# Power_Distribution_-_Charger_and_Rear_Ca.net
KiCad netlist of a schematic drawn in Altium Designer
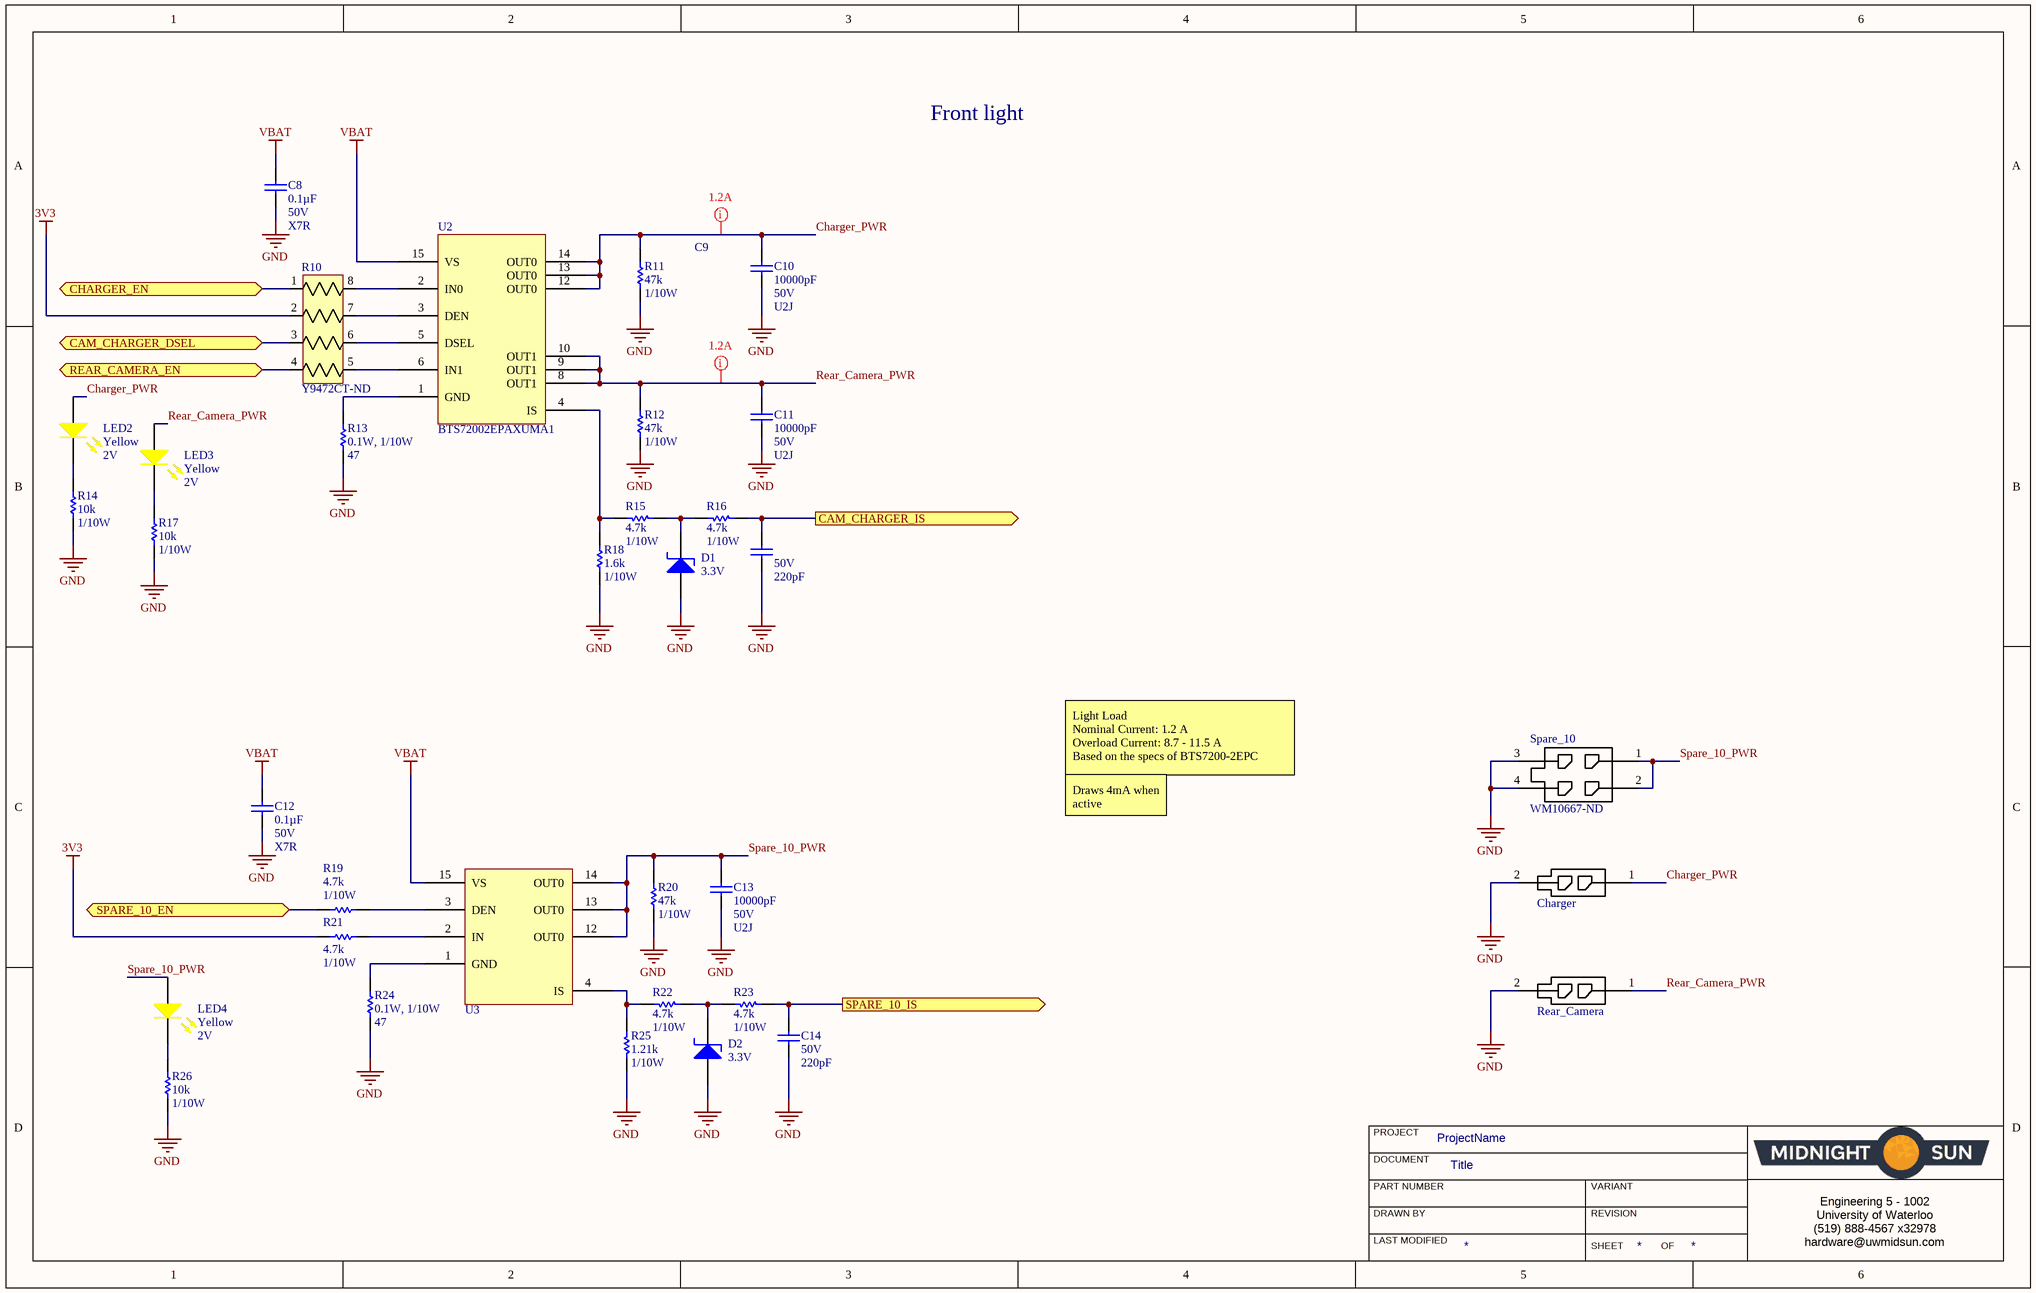
[diagram p0: Power Distribution - Charger and Rear Camera.SchDoc]

(export (version "E")
  (design (tool "Eeschema 10.0.6"))
  (components
    (comp (ref "C8")
      (value "CAP CER 0.1UF 50V 10% X7R 0603")
      (footprint "CAP, 0603")
      (description "0.10µF ±10% 50V Ceramic Capacitor X7R 0603 (1608 Metric)")
      (fields
        (field (name "TOLERANCE") "±10%")
        (field (name "CAPACITANCE") "0.1µF")
        (field (name "VOLTAGE") "50V")
        (field (name "TEMPERATURE COEFFICIENT") "X7R")
      )
      (libsource (lib "Schematic Diagrams") (part "CAP CER 0.1UF 50V 10% X7R 0603"))
    )
    (comp (ref "C9")
      (value "CAP CER 220PF 50V C0G/NP0 0603")
      (footprint "CAP, 0603")
      (description "220pF ±5% 50V Ceramic Capacitor C0G, NP0 0603 (1608 Metric)")
      (fields
        (field (name "MANUFACTURER") "KEMET")
        (field (name "TOLERANCE") "5%")
        (field (name "VOLTAGE RATING") "50V")
        (field (name "CAPACITANCE") "220pF")
      )
      (libsource (lib "Schematic Diagrams") (part "CAP CER 220PF 50V C0G/NP0 0603"))
    )
    (comp (ref "C10")
      (value "CAP CER 10nF 50V 5% X7R 0603")
      (footprint "CAP, 0603")
      (description "10000pF ±5% 50V Ceramic Capacitor U2J 0603 (1608 Metric)")
      (fields
        (field (name "TOLERANCE") "±5%")
        (field (name "CAPACITANCE") "10000pF")
        (field (name "VOLTAGE") "50V")
        (field (name "TEMPERATURE COEFFICIENT") "U2J")
      )
      (libsource (lib "Schematic Diagrams") (part "CAP CER 10nF 50V 5% X7R 0603"))
    )
    (comp (ref "C11")
      (value "CAP CER 10nF 50V 5% X7R 0603")
      (footprint "CAP, 0603")
      (description "10000pF ±5% 50V Ceramic Capacitor U2J 0603 (1608 Metric)")
      (fields
        (field (name "TOLERANCE") "±5%")
        (field (name "CAPACITANCE") "10000pF")
        (field (name "VOLTAGE") "50V")
        (field (name "TEMPERATURE COEFFICIENT") "U2J")
      )
      (libsource (lib "Schematic Diagrams") (part "CAP CER 10nF 50V 5% X7R 0603"))
    )
    (comp (ref "C12")
      (value "CAP CER 0.1UF 50V 10% X7R 0603")
      (footprint "CAP, 0603")
      (description "0.10µF ±10% 50V Ceramic Capacitor X7R 0603 (1608 Metric)")
      (fields
        (field (name "TOLERANCE") "±10%")
        (field (name "CAPACITANCE") "0.1µF")
        (field (name "VOLTAGE") "50V")
        (field (name "TEMPERATURE COEFFICIENT") "X7R")
      )
      (libsource (lib "Schematic Diagrams") (part "CAP CER 0.1UF 50V 10% X7R 0603"))
    )
    (comp (ref "C13")
      (value "CAP CER 10nF 50V 5% X7R 0603")
      (footprint "CAP, 0603")
      (description "10000pF ±5% 50V Ceramic Capacitor U2J 0603 (1608 Metric)")
      (fields
        (field (name "TOLERANCE") "±5%")
        (field (name "CAPACITANCE") "10000pF")
        (field (name "VOLTAGE") "50V")
        (field (name "TEMPERATURE COEFFICIENT") "U2J")
      )
      (libsource (lib "Schematic Diagrams") (part "CAP CER 10nF 50V 5% X7R 0603"))
    )
    (comp (ref "C14")
      (value "CAP CER 220PF 50V C0G/NP0 0603")
      (footprint "CAP, 0603")
      (description "220pF ±5% 50V Ceramic Capacitor C0G, NP0 0603 (1608 Metric)")
      (fields
        (field (name "MANUFACTURER") "KEMET")
        (field (name "TOLERANCE") "5%")
        (field (name "VOLTAGE RATING") "50V")
        (field (name "CAPACITANCE") "220pF")
      )
      (libsource (lib "Schematic Diagrams") (part "CAP CER 220PF 50V C0G/NP0 0603"))
    )
    (comp (ref "Charger")
      (value "CONN 2POS MICRO-FIT 3mm")
      (footprint "CONN, 2POS MICRO-FIT")
      (description "Connector Header Through Hole 2 position")
      (fields (field (name "MANUFACTURER") "Molex") (field (name "MANUFACTURER PART NUMBER") "43045-0227"))
      (libsource (lib "Schematic Diagrams") (part "CONN 2POS MICRO-FIT 3mm"))
    )
    (comp (ref "D1")
      (value "DIODE ZENER 3.3V 200MW SOD323")
      (footprint "sod-323")
      (description "Zener Diode 3.3V 200mW ±5% Surface Mount SOD-323")
      (fields (field (name "VOLTAGE") "3.3V"))
      (libsource (lib "Schematic Diagrams") (part "DIODE ZENER 3.3V 200MW SOD323"))
    )
    (comp (ref "D2")
      (value "DIODE ZENER 3.3V 200MW SOD323")
      (footprint "sod-323")
      (description "Zener Diode 3.3V 200mW ±5% Surface Mount SOD-323")
      (fields (field (name "VOLTAGE") "3.3V"))
      (libsource (lib "Schematic Diagrams") (part "DIODE ZENER 3.3V 200MW SOD323"))
    )
    (comp (ref "LED2")
      (value "LED YELLOW CLEAR 2.1V 0603")
      (footprint "LED_0603")
      (description "Yellow 590nm LED Indication - Discrete 2V 0603 (1608 Metric)")
      (fields
        (field (name "MANUFACTURER") "Wurth Electronics Inc.")
        (field (name "MANUFACTURER PART NUMBER") "150060YS75000")
        (field (name "COLOR") "Yellow")
        (field (name "VOLTAGE - FORWARD (VF) (TYP)") "2V")
      )
      (libsource (lib "Schematic Diagrams") (part "LED YELLOW CLEAR 2.1V 0603"))
    )
    (comp (ref "LED3")
      (value "LED YELLOW CLEAR 2.1V 0603")
      (footprint "LED_0603")
      (description "Yellow 590nm LED Indication - Discrete 2V 0603 (1608 Metric)")
      (fields
        (field (name "MANUFACTURER") "Wurth Electronics Inc.")
        (field (name "MANUFACTURER PART NUMBER") "150060YS75000")
        (field (name "COLOR") "Yellow")
        (field (name "VOLTAGE - FORWARD (VF) (TYP)") "2V")
      )
      (libsource (lib "Schematic Diagrams") (part "LED YELLOW CLEAR 2.1V 0603"))
    )
    (comp (ref "LED4")
      (value "LED YELLOW CLEAR 2.1V 0603")
      (footprint "LED_0603")
      (description "Yellow 590nm LED Indication - Discrete 2V 0603 (1608 Metric)")
      (fields
        (field (name "MANUFACTURER") "Wurth Electronics Inc.")
        (field (name "MANUFACTURER PART NUMBER") "150060YS75000")
        (field (name "COLOR") "Yellow")
        (field (name "VOLTAGE - FORWARD (VF) (TYP)") "2V")
      )
      (libsource (lib "Schematic Diagrams") (part "LED YELLOW CLEAR 2.1V 0603"))
    )
    (comp (ref "R10")
      (value "RES ARRAY 4 RES 4.7K OHM 1206")
      (footprint "RES ARRAY 4RES 1206")
      (fields (field (name "TOLERANCE") "±5%") (field (name "SUPPLIER PART NUMBER 1") "Y9472CT-ND"))
      (libsource (lib "Schematic Diagrams") (part "RES ARRAY 4 RES 4.7K OHM 1206"))
    )
    (comp (ref "R11")
      (value "RES 47K OHM 1% 1/10W 0603")
      (footprint "RES, 0603")
      (description "47 kOhms ±1% 0.1W, 1/10W Chip Resistor 0603 (1608 Metric) Automotive AEC-Q200 Thick Film")
      (fields
        (field (name "MANUFACTURER") "Panasonic")
        (field (name "MANUFACTURER PART NUMBER") "ERJ3EKF4702V")
        (field (name "RESISTANCE") "47k")
        (field (name "POWER RATING") "1/10W")
      )
      (libsource (lib "Schematic Diagrams") (part "RES 47K OHM 1% 1/10W 0603"))
    )
    (comp (ref "R12")
      (value "RES 47K OHM 1% 1/10W 0603")
      (footprint "RES, 0603")
      (description "47 kOhms ±1% 0.1W, 1/10W Chip Resistor 0603 (1608 Metric) Automotive AEC-Q200 Thick Film")
      (fields
        (field (name "MANUFACTURER") "Panasonic")
        (field (name "MANUFACTURER PART NUMBER") "ERJ3EKF4702V")
        (field (name "RESISTANCE") "47k")
        (field (name "POWER RATING") "1/10W")
      )
      (libsource (lib "Schematic Diagrams") (part "RES 47K OHM 1% 1/10W 0603"))
    )
    (comp (ref "R13")
      (value "RES SMD 47 OHM 1% 1/10W 0603")
      (footprint "RES, 0603")
      (fields
        (field (name "TOLERANCE") "±1%")
        (field (name "POWER (WATTS)") "0.1W, 1/10W")
        (field (name "VALUES") "47")
      )
      (libsource (lib "Schematic Diagrams") (part "RES SMD 47 OHM 1% 1/10W 0603"))
    )
    (comp (ref "R14")
      (value "RES 10K OHM 1% 1/10W 0603")
      (footprint "RES, 0603")
      (description "RES SMD 10K OHM 1% 1/10W 0603")
      (fields
        (field (name "TOLERANCE") "±1%")
        (field (name "RESISTANCE") "10k")
        (field (name "POWER") "1/10W")
      )
      (libsource (lib "Schematic Diagrams") (part "RES 10K OHM 1% 1/10W 0603"))
    )
    (comp (ref "R15")
      (value "RES 4.7K OHM 1% 1/10W 0603")
      (footprint "RES, 0603")
      (description "4.7k Ohm ±1% 0.1W, 1/10W Chip Resistor 0603 (1608 Metric) Moisture Resistant Thick Film")
      (fields
        (field (name "TOLERANCE") "±1%")
        (field (name "RESISTANCE (OHMS)") "4.7k")
        (field (name "POWER (WATTS)") "1/10W")
      )
      (libsource (lib "Schematic Diagrams") (part "RES 4.7K OHM 1% 1/10W 0603"))
    )
    (comp (ref "R16")
      (value "RES 4.7K OHM 1% 1/10W 0603")
      (footprint "RES, 0603")
      (description "4.7k Ohm ±1% 0.1W, 1/10W Chip Resistor 0603 (1608 Metric) Moisture Resistant Thick Film")
      (fields
        (field (name "TOLERANCE") "±1%")
        (field (name "RESISTANCE (OHMS)") "4.7k")
        (field (name "POWER (WATTS)") "1/10W")
      )
      (libsource (lib "Schematic Diagrams") (part "RES 4.7K OHM 1% 1/10W 0603"))
    )
    (comp (ref "R17")
      (value "RES 10K OHM 1% 1/10W 0603")
      (footprint "RES, 0603")
      (description "RES SMD 10K OHM 1% 1/10W 0603")
      (fields
        (field (name "TOLERANCE") "±1%")
        (field (name "RESISTANCE") "10k")
        (field (name "POWER") "1/10W")
      )
      (libsource (lib "Schematic Diagrams") (part "RES 10K OHM 1% 1/10W 0603"))
    )
    (comp (ref "R18")
      (value "RES 1.6K OHM 1% 1/10W 0603")
      (footprint "RES, 0603")
      (description "1.6 kOhms ±1% 0.1W, 1/10W Chip Resistor 0603 (1608 Metric) Moisture Resistant Thick Film")
      (fields
        (field (name "MANUFACTURER") "Yageo")
        (field (name "MANUFACTURER PART NUMBER") "RC0603FR-071K6L")
        (field (name "RESISTANCE") "1.6k")
        (field (name "POWER RATING") "1/10W")
      )
      (libsource (lib "Schematic Diagrams") (part "RES 1.6K OHM 1% 1/10W 0603"))
    )
    (comp (ref "R19")
      (value "RES 4.7K OHM 1% 1/10W 0603")
      (footprint "RES, 0603")
      (description "4.7k Ohm ±1% 0.1W, 1/10W Chip Resistor 0603 (1608 Metric) Moisture Resistant Thick Film")
      (fields
        (field (name "TOLERANCE") "±1%")
        (field (name "RESISTANCE (OHMS)") "4.7k")
        (field (name "POWER (WATTS)") "1/10W")
      )
      (libsource (lib "Schematic Diagrams") (part "RES 4.7K OHM 1% 1/10W 0603"))
    )
    (comp (ref "R20")
      (value "RES 47K OHM 1% 1/10W 0603")
      (footprint "RES, 0603")
      (description "47 kOhms ±1% 0.1W, 1/10W Chip Resistor 0603 (1608 Metric) Automotive AEC-Q200 Thick Film")
      (fields
        (field (name "MANUFACTURER") "Panasonic")
        (field (name "MANUFACTURER PART NUMBER") "ERJ3EKF4702V")
        (field (name "RESISTANCE") "47k")
        (field (name "POWER RATING") "1/10W")
      )
      (libsource (lib "Schematic Diagrams") (part "RES 47K OHM 1% 1/10W 0603"))
    )
    (comp (ref "R21")
      (value "RES 4.7K OHM 1% 1/10W 0603")
      (footprint "RES, 0603")
      (description "4.7k Ohm ±1% 0.1W, 1/10W Chip Resistor 0603 (1608 Metric) Moisture Resistant Thick Film")
      (fields
        (field (name "TOLERANCE") "±1%")
        (field (name "RESISTANCE (OHMS)") "4.7k")
        (field (name "POWER (WATTS)") "1/10W")
      )
      (libsource (lib "Schematic Diagrams") (part "RES 4.7K OHM 1% 1/10W 0603"))
    )
    (comp (ref "R22")
      (value "RES 4.7K OHM 1% 1/10W 0603")
      (footprint "RES, 0603")
      (description "4.7k Ohm ±1% 0.1W, 1/10W Chip Resistor 0603 (1608 Metric) Moisture Resistant Thick Film")
      (fields
        (field (name "TOLERANCE") "±1%")
        (field (name "RESISTANCE (OHMS)") "4.7k")
        (field (name "POWER (WATTS)") "1/10W")
      )
      (libsource (lib "Schematic Diagrams") (part "RES 4.7K OHM 1% 1/10W 0603"))
    )
    (comp (ref "R23")
      (value "RES 4.7K OHM 1% 1/10W 0603")
      (footprint "RES, 0603")
      (description "4.7k Ohm ±1% 0.1W, 1/10W Chip Resistor 0603 (1608 Metric) Moisture Resistant Thick Film")
      (fields
        (field (name "TOLERANCE") "±1%")
        (field (name "RESISTANCE (OHMS)") "4.7k")
        (field (name "POWER (WATTS)") "1/10W")
      )
      (libsource (lib "Schematic Diagrams") (part "RES 4.7K OHM 1% 1/10W 0603"))
    )
    (comp (ref "R24")
      (value "RES SMD 47 OHM 1% 1/10W 0603")
      (footprint "RES, 0603")
      (fields
        (field (name "TOLERANCE") "±1%")
        (field (name "POWER (WATTS)") "0.1W, 1/10W")
        (field (name "VALUES") "47")
      )
      (libsource (lib "Schematic Diagrams") (part "RES SMD 47 OHM 1% 1/10W 0603"))
    )
    (comp (ref "R25")
      (value "RES 1.21K OHM 1% 1/10W 0603")
      (footprint "RES, 0603")
      (description "1.21k Ohm ±1% 0.1W, 1/10W Chip Resistor 0603 (1608 Metric) Moisture Resistant Thick Film")
      (fields
        (field (name "TOLERANCE") "±1%")
        (field (name "RESISTANCE") "1.21k")
        (field (name "POWER") "1/10W")
      )
      (libsource (lib "Schematic Diagrams") (part "RES 1.21K OHM 1% 1/10W 0603"))
    )
    (comp (ref "R26")
      (value "RES 10K OHM 1% 1/10W 0603")
      (footprint "RES, 0603")
      (description "RES SMD 10K OHM 1% 1/10W 0603")
      (fields
        (field (name "TOLERANCE") "±1%")
        (field (name "RESISTANCE") "10k")
        (field (name "POWER") "1/10W")
      )
      (libsource (lib "Schematic Diagrams") (part "RES 10K OHM 1% 1/10W 0603"))
    )
    (comp (ref "Rear_Camera")
      (value "CONN 2POS MICRO-FIT 3mm")
      (footprint "CONN, 2POS MICRO-FIT")
      (description "Connector Header Through Hole 2 position")
      (fields (field (name "MANUFACTURER") "Molex") (field (name "MANUFACTURER PART NUMBER") "43045-0227"))
      (libsource (lib "Schematic Diagrams") (part "CONN 2POS MICRO-FIT 3mm"))
    )
    (comp (ref "Spare_10")
      (value "CONN 4POS MICRO-FIT 3mm")
      (footprint "CONN 4POS MICROFIT (2x2)")
      (fields
        (field (name "MANUFACTURER") "Molex, LLC")
        (field (name "MANUFACTURER PART NUMBER") "430450427")
        (field (name "SUPPLIER PART NUMBER 1") "WM10667-ND")
      )
      (libsource (lib "Schematic Diagrams") (part "CONN 4POS MICRO-FIT 3mm"))
    )
    (comp (ref "U2")
      (value "IC LOAD SWITCH BTS7200-2EPA PG-TSDSO-14_1")
      (footprint "IC LOAD SWITCH PG-TSDSO-14-22")
      (description "Power Switch/Driver 1:1 N-Channel 1.2A PG-TSDSO-14-22")
      (fields
        (field (name "MANUFACTURER") "Infineon")
        (field (name "MANUFACTURER PART NUMBER") "BTS72002EPAXUMA1")
      )
      (libsource (lib "Schematic Diagrams") (part "IC LOAD SWITCH BTS7200-2EPA PG-TSDSO-14_1"))
    )
    (comp (ref "U3")
      (value "IC LOAD SWITCH BTS70401EPA PG-TSDSO-14-22")
      (footprint "IC LOAD SWITCH PG-TSDSO-14-22")
      (description "Power Switch/Driver 1:1 N-Channel 4.5A PG-TSDSO-14-22")
      (fields
        (field (name "MANUFACTURER") "Infineon")
        (field (name "MANUFACTURER PART NUMBER") "BTS70401EPAXUMA1")
      )
      (libsource (lib "Schematic Diagrams") (part "IC LOAD SWITCH BTS70401EPA PG-TSDSO-14-22"))
    )
  )
  (nets
    (net (code "1") (name "/CAM_CHARGER_DSEL") (class "Default")
      (node (ref "R10") (pin "3") (pinfunction "3_3") (pintype "passive"))
    )
    (net (code "2") (name "/CAM_CHARGER_IS") (class "Default")
      (node (ref "C9") (pin "1") (pinfunction "1_1") (pintype "passive"))
      (node (ref "R16") (pin "1") (pinfunction "1_1") (pintype "passive"))
    )
    (net (code "3") (name "/CHARGER_EN") (class "Default")
      (node (ref "R10") (pin "1") (pinfunction "1_1") (pintype "passive"))
    )
    (net (code "4") (name "/Charger_PWR") (class "Default")
      (node (ref "C10") (pin "1") (pinfunction "1_1") (pintype "passive"))
      (node (ref "Charger") (pin "1") (pinfunction "1_1") (pintype "passive"))
      (node (ref "LED2") (pin "1") (pinfunction "A_1") (pintype "passive"))
      (node (ref "R11") (pin "1") (pinfunction "1_1") (pintype "passive"))
      (node (ref "U2") (pin "12") (pinfunction "OUT0_12") (pintype "passive"))
      (node (ref "U2") (pin "13") (pinfunction "OUT0_13") (pintype "passive"))
      (node (ref "U2") (pin "14") (pinfunction "OUT0_14") (pintype "passive"))
    )
    (net (code "5") (name "/REAR_CAMERA_EN") (class "Default")
      (node (ref "R10") (pin "4") (pinfunction "4_4") (pintype "passive"))
    )
    (net (code "6") (name "/Rear_Camera_PWR") (class "Default")
      (node (ref "C11") (pin "1") (pinfunction "1_1") (pintype "passive"))
      (node (ref "LED3") (pin "1") (pinfunction "A_1") (pintype "passive"))
      (node (ref "R12") (pin "1") (pinfunction "1_1") (pintype "passive"))
      (node (ref "Rear_Camera") (pin "1") (pinfunction "1_1") (pintype "passive"))
      (node (ref "U2") (pin "10") (pinfunction "OUT1_10") (pintype "passive"))
      (node (ref "U2") (pin "8") (pinfunction "OUT1_8") (pintype "passive"))
      (node (ref "U2") (pin "9") (pinfunction "OUT1_9") (pintype "passive"))
    )
    (net (code "7") (name "/SPARE_10_EN") (class "Default")
      (node (ref "R19") (pin "1") (pinfunction "1_1") (pintype "passive"))
    )
    (net (code "8") (name "/SPARE_10_IS") (class "Default")
      (node (ref "C14") (pin "1") (pinfunction "1_1") (pintype "passive"))
      (node (ref "R23") (pin "1") (pinfunction "1_1") (pintype "passive"))
    )
    (net (code "9") (name "/Spare_10_PWR") (class "Default")
      (node (ref "C13") (pin "1") (pinfunction "1_1") (pintype "passive"))
      (node (ref "LED4") (pin "1") (pinfunction "A_1") (pintype "passive"))
      (node (ref "R20") (pin "1") (pinfunction "1_1") (pintype "passive"))
      (node (ref "Spare_10") (pin "1") (pinfunction "1_1") (pintype "passive"))
      (node (ref "Spare_10") (pin "2") (pinfunction "2_2") (pintype "passive"))
      (node (ref "U3") (pin "12") (pinfunction "OUT0_12") (pintype "passive"))
      (node (ref "U3") (pin "13") (pinfunction "OUT0_13") (pintype "passive"))
      (node (ref "U3") (pin "14") (pinfunction "OUT0_14") (pintype "passive"))
    )
    (net (code "10") (name "3V3") (class "Default")
      (node (ref "R10") (pin "2") (pinfunction "2_2") (pintype "passive"))
      (node (ref "R21") (pin "1") (pinfunction "1_1") (pintype "passive"))
    )
    (net (code "11") (name "GND") (class "Default")
      (node (ref "C10") (pin "2") (pinfunction "2_2") (pintype "passive"))
      (node (ref "C11") (pin "2") (pinfunction "2_2") (pintype "passive"))
      (node (ref "C12") (pin "2") (pinfunction "2_2") (pintype "passive"))
      (node (ref "C13") (pin "2") (pinfunction "2_2") (pintype "passive"))
      (node (ref "C14") (pin "2") (pinfunction "2_2") (pintype "passive"))
      (node (ref "C8") (pin "2") (pinfunction "2_2") (pintype "passive"))
      (node (ref "C9") (pin "2") (pinfunction "2_2") (pintype "passive"))
      (node (ref "Charger") (pin "2") (pinfunction "2_2") (pintype "passive"))
      (node (ref "D1") (pin "1") (pinfunction "A_1") (pintype "passive"))
      (node (ref "D2") (pin "1") (pinfunction "A_1") (pintype "passive"))
      (node (ref "R11") (pin "2") (pinfunction "2_2") (pintype "passive"))
      (node (ref "R12") (pin "2") (pinfunction "2_2") (pintype "passive"))
      (node (ref "R13") (pin "2") (pinfunction "2_2") (pintype "passive"))
      (node (ref "R14") (pin "2") (pinfunction "2_2") (pintype "passive"))
      (node (ref "R17") (pin "2") (pinfunction "2_2") (pintype "passive"))
      (node (ref "R18") (pin "2") (pinfunction "2_2") (pintype "passive"))
      (node (ref "R20") (pin "2") (pinfunction "2_2") (pintype "passive"))
      (node (ref "R24") (pin "2") (pinfunction "2_2") (pintype "passive"))
      (node (ref "R25") (pin "2") (pinfunction "2_2") (pintype "passive"))
      (node (ref "R26") (pin "2") (pinfunction "2_2") (pintype "passive"))
      (node (ref "Rear_Camera") (pin "2") (pinfunction "2_2") (pintype "passive"))
      (node (ref "Spare_10") (pin "3") (pinfunction "3_3") (pintype "passive"))
      (node (ref "Spare_10") (pin "4") (pinfunction "4_4") (pintype "passive"))
    )
    (net (code "12") (name "Net-(D1-K)") (class "Default")
      (node (ref "D1") (pin "2") (pinfunction "K_2") (pintype "passive"))
      (node (ref "R15") (pin "1") (pinfunction "1_1") (pintype "passive"))
      (node (ref "R16") (pin "2") (pinfunction "2_2") (pintype "passive"))
    )
    (net (code "13") (name "Net-(D2-K)") (class "Default")
      (node (ref "D2") (pin "2") (pinfunction "K_2") (pintype "passive"))
      (node (ref "R22") (pin "1") (pinfunction "1_1") (pintype "passive"))
      (node (ref "R23") (pin "2") (pinfunction "2_2") (pintype "passive"))
    )
    (net (code "14") (name "Net-(LED2-K)") (class "Default")
      (node (ref "LED2") (pin "2") (pinfunction "K_2") (pintype "passive"))
      (node (ref "R14") (pin "1") (pinfunction "1_1") (pintype "passive"))
    )
    (net (code "15") (name "Net-(LED3-K)") (class "Default")
      (node (ref "LED3") (pin "2") (pinfunction "K_2") (pintype "passive"))
      (node (ref "R17") (pin "1") (pinfunction "1_1") (pintype "passive"))
    )
    (net (code "16") (name "Net-(LED4-K)") (class "Default")
      (node (ref "LED4") (pin "2") (pinfunction "K_2") (pintype "passive"))
      (node (ref "R26") (pin "1") (pinfunction "1_1") (pintype "passive"))
    )
    (net (code "17") (name "Net-(U2-DEN)") (class "Default")
      (node (ref "R10") (pin "7") (pinfunction "7_7") (pintype "passive"))
      (node (ref "U2") (pin "3") (pinfunction "DEN_3") (pintype "passive"))
    )
    (net (code "18") (name "Net-(U2-DSEL)") (class "Default")
      (node (ref "R10") (pin "6") (pinfunction "6_6") (pintype "passive"))
      (node (ref "U2") (pin "5") (pinfunction "DSEL_5") (pintype "passive"))
    )
    (net (code "19") (name "Net-(U2-GND)") (class "Default")
      (node (ref "R13") (pin "1") (pinfunction "1_1") (pintype "passive"))
      (node (ref "U2") (pin "1") (pinfunction "GND_1") (pintype "passive"))
    )
    (net (code "20") (name "Net-(U2-IN0)") (class "Default")
      (node (ref "R10") (pin "8") (pinfunction "8_8") (pintype "passive"))
      (node (ref "U2") (pin "2") (pinfunction "IN0_2") (pintype "passive"))
    )
    (net (code "21") (name "Net-(U2-IN1)") (class "Default")
      (node (ref "R10") (pin "5") (pinfunction "5_5") (pintype "passive"))
      (node (ref "U2") (pin "6") (pinfunction "IN1_6") (pintype "passive"))
    )
    (net (code "22") (name "Net-(U2-IS)") (class "Default")
      (node (ref "R15") (pin "2") (pinfunction "2_2") (pintype "passive"))
      (node (ref "R18") (pin "1") (pinfunction "1_1") (pintype "passive"))
      (node (ref "U2") (pin "4") (pinfunction "IS_4") (pintype "passive"))
    )
    (net (code "23") (name "Net-(U3-DEN)") (class "Default")
      (node (ref "R19") (pin "2") (pinfunction "2_2") (pintype "passive"))
      (node (ref "U3") (pin "3") (pinfunction "DEN_3") (pintype "passive"))
    )
    (net (code "24") (name "Net-(U3-GND)") (class "Default")
      (node (ref "R24") (pin "1") (pinfunction "1_1") (pintype "passive"))
      (node (ref "U3") (pin "1") (pinfunction "GND_1") (pintype "passive"))
    )
    (net (code "25") (name "Net-(U3-IN)") (class "Default")
      (node (ref "R21") (pin "2") (pinfunction "2_2") (pintype "passive"))
      (node (ref "U3") (pin "2") (pinfunction "IN_2") (pintype "passive"))
    )
    (net (code "26") (name "Net-(U3-IS)") (class "Default")
      (node (ref "R22") (pin "2") (pinfunction "2_2") (pintype "passive"))
      (node (ref "R25") (pin "1") (pinfunction "1_1") (pintype "passive"))
      (node (ref "U3") (pin "4") (pinfunction "IS_4") (pintype "passive"))
    )
    (net (code "27") (name "VBAT") (class "Default")
      (node (ref "C12") (pin "1") (pinfunction "1_1") (pintype "passive"))
      (node (ref "C8") (pin "1") (pinfunction "1_1") (pintype "passive"))
      (node (ref "U2") (pin "15") (pinfunction "VS_15") (pintype "passive"))
      (node (ref "U3") (pin "15") (pinfunction "VS_15") (pintype "passive"))
    )
  )
)
